# motherboard_v1.net
KiCad netlist of a schematic drawn in EAGLE
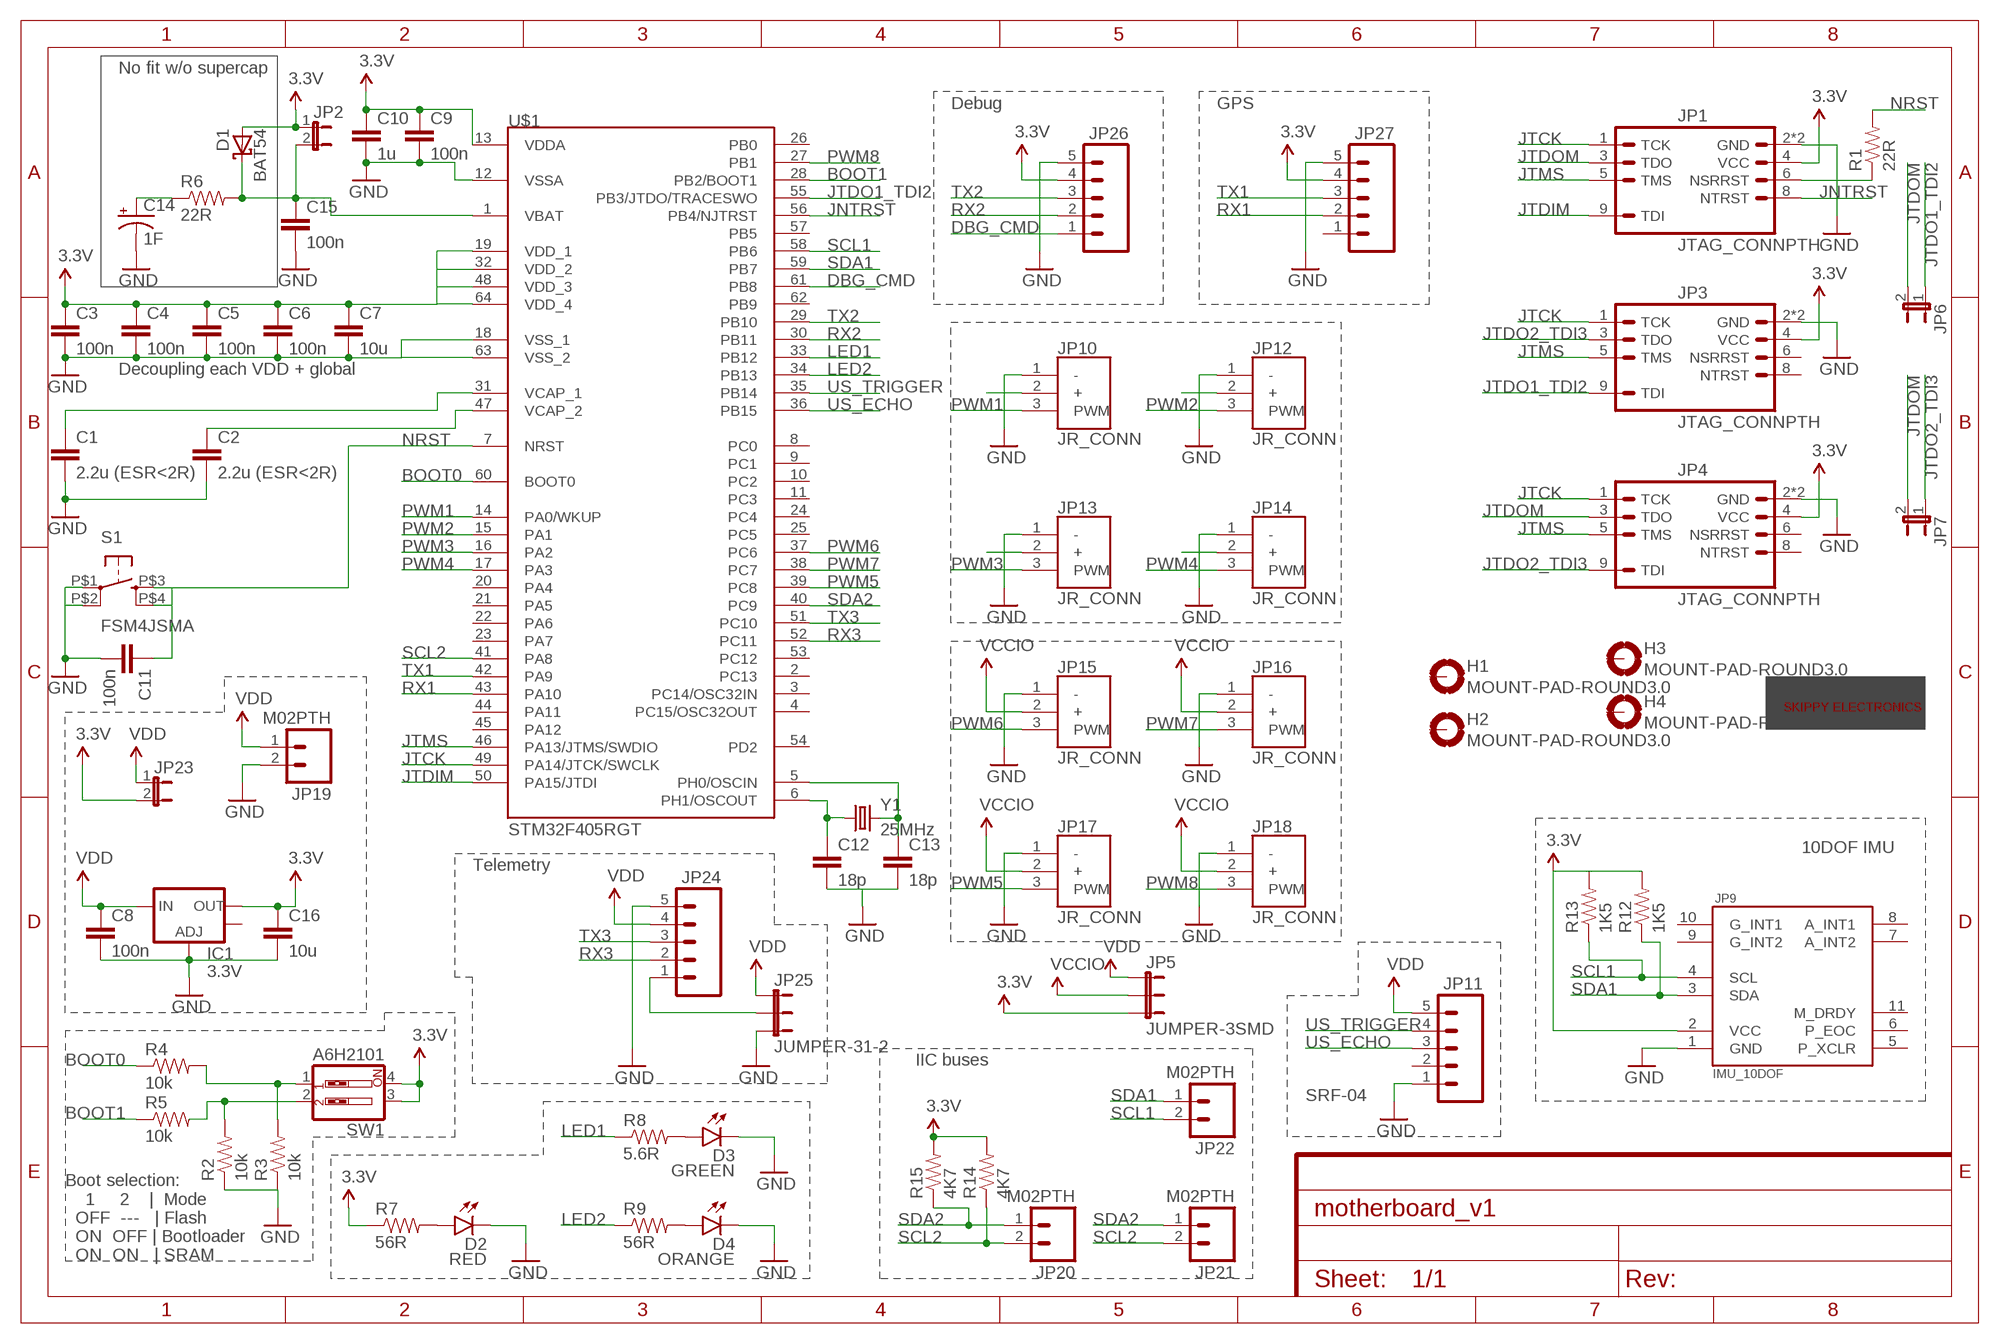
[diagram p0: schematic, sheet 1]

(export (version "E")
  (design (tool "Eeschema 10.0.6"))
  (components
    (comp (ref "C1")
      (value "2.2u (ESR<2R)")
      (footprint "eagle-import:1206")
      (libsource (lib "eagle-import") (part "CAP1206"))
    )
    (comp (ref "C2")
      (value "2.2u (ESR<2R)")
      (footprint "eagle-import:1206")
      (libsource (lib "eagle-import") (part "CAP1206"))
    )
    (comp (ref "C3")
      (value "100n")
      (footprint "eagle-import:0805")
      (libsource (lib "eagle-import") (part "CAP0805"))
    )
    (comp (ref "C4")
      (value "100n")
      (footprint "eagle-import:0805")
      (libsource (lib "eagle-import") (part "CAP0805"))
    )
    (comp (ref "C5")
      (value "100n")
      (footprint "eagle-import:0805")
      (libsource (lib "eagle-import") (part "CAP0805"))
    )
    (comp (ref "C6")
      (value "100n")
      (footprint "eagle-import:0805")
      (libsource (lib "eagle-import") (part "CAP0805"))
    )
    (comp (ref "C7")
      (value "10u")
      (footprint "eagle-import:1206")
      (libsource (lib "eagle-import") (part "CAP1206"))
    )
    (comp (ref "C8")
      (value "100n")
      (footprint "eagle-import:1206")
      (libsource (lib "eagle-import") (part "CAP1206"))
    )
    (comp (ref "C9")
      (value "100n")
      (footprint "eagle-import:0805")
      (libsource (lib "eagle-import") (part "CAP0805"))
    )
    (comp (ref "C10")
      (value "1u")
      (footprint "eagle-import:1206")
      (libsource (lib "eagle-import") (part "CAP1206"))
    )
    (comp (ref "C11")
      (value "100n")
      (footprint "eagle-import:1206")
      (libsource (lib "eagle-import") (part "CAP1206"))
    )
    (comp (ref "C12")
      (value "18p")
      (footprint "eagle-import:1206")
      (libsource (lib "eagle-import") (part "CAP1206"))
    )
    (comp (ref "C13")
      (value "18p")
      (footprint "eagle-import:1206")
      (libsource (lib "eagle-import") (part "CAP1206"))
    )
    (comp (ref "C14")
      (value "1F")
      (footprint "eagle-import:CPOL-RADIAL-D165-P508")
      (libsource (lib "eagle-import") (part "SUPERCAP"))
    )
    (comp (ref "C15")
      (value "100n")
      (footprint "eagle-import:0805")
      (libsource (lib "eagle-import") (part "CAP0805"))
    )
    (comp (ref "C16")
      (value "10u")
      (footprint "eagle-import:1206")
      (libsource (lib "eagle-import") (part "CAP1206"))
    )
    (comp (ref "D1")
      (value "BAT54")
      (footprint "eagle-import:SOT23")
      (libsource (lib "eagle-import") (part "BAT54"))
    )
    (comp (ref "D2")
      (value "RED")
      (footprint "eagle-import:LED-1206")
      (libsource (lib "eagle-import") (part "LED1206"))
    )
    (comp (ref "D3")
      (value "GREEN")
      (footprint "eagle-import:LED-1206")
      (libsource (lib "eagle-import") (part "LED1206"))
    )
    (comp (ref "D4")
      (value "ORANGE")
      (footprint "eagle-import:LED-1206")
      (libsource (lib "eagle-import") (part "LED1206"))
    )
    (comp (ref "H1")
      (value "MOUNT-PAD-ROUND3.0")
      (footprint "eagle-import:3,0-PAD")
      (libsource (lib "eagle-import") (part "MOUNT-PAD-ROUND3.0"))
    )
    (comp (ref "H2")
      (value "MOUNT-PAD-ROUND3.0")
      (footprint "eagle-import:3,0-PAD")
      (libsource (lib "eagle-import") (part "MOUNT-PAD-ROUND3.0"))
    )
    (comp (ref "H3")
      (value "MOUNT-PAD-ROUND3.0")
      (footprint "eagle-import:3,0-PAD")
      (libsource (lib "eagle-import") (part "MOUNT-PAD-ROUND3.0"))
    )
    (comp (ref "H4")
      (value "MOUNT-PAD-ROUND3.0")
      (footprint "eagle-import:3,0-PAD")
      (libsource (lib "eagle-import") (part "MOUNT-PAD-ROUND3.0"))
    )
    (comp (ref "IC1")
      (value "3.3V")
      (footprint "eagle-import:SOT223")
      (libsource (lib "eagle-import") (part "V_REG_LM1117SOT223"))
    )
    (comp (ref "JP1")
      (value "JTAG_CONNPTH")
      (footprint "eagle-import:AVR_ICSP")
      (libsource (lib "eagle-import") (part "JTAG_CONNPTH"))
    )
    (comp (ref "JP2")
      (value "JUMPER-2SMD-NO")
      (footprint "eagle-import:SJ_2S-NO")
      (libsource (lib "eagle-import") (part "JUMPER-2SMD-NO"))
    )
    (comp (ref "JP3")
      (value "JTAG_CONNPTH")
      (footprint "eagle-import:AVR_ICSP")
      (libsource (lib "eagle-import") (part "JTAG_CONNPTH"))
    )
    (comp (ref "JP4")
      (value "JTAG_CONNPTH")
      (footprint "eagle-import:AVR_ICSP")
      (libsource (lib "eagle-import") (part "JTAG_CONNPTH"))
    )
    (comp (ref "JP5")
      (value "JUMPER-3SMD")
      (footprint "eagle-import:SJ_3")
      (libsource (lib "eagle-import") (part "JUMPER-3SMD"))
    )
    (comp (ref "JP6")
      (value "JUMPER-2SMD-NO")
      (footprint "eagle-import:SJ_2S-NO")
      (libsource (lib "eagle-import") (part "JUMPER-2SMD-NO"))
    )
    (comp (ref "JP7")
      (value "JUMPER-2SMD-NO")
      (footprint "eagle-import:SJ_2S-NO")
      (libsource (lib "eagle-import") (part "JUMPER-2SMD-NO"))
    )
    (comp (ref "JP9")
      (value "IMU_10DOF")
      (footprint "eagle-import:IMU_10DOF")
      (libsource (lib "eagle-import") (part "IMU_10DOF"))
    )
    (comp (ref "JP10")
      (value "JR_CONN")
      (footprint "eagle-import:1X03")
      (libsource (lib "eagle-import") (part "JR_CONN"))
    )
    (comp (ref "JP11")
      (value "M05PTH")
      (footprint "eagle-import:1X05")
      (libsource (lib "eagle-import") (part "M05PTH"))
    )
    (comp (ref "JP12")
      (value "JR_CONN")
      (footprint "eagle-import:1X03")
      (libsource (lib "eagle-import") (part "JR_CONN"))
    )
    (comp (ref "JP13")
      (value "JR_CONN")
      (footprint "eagle-import:1X03")
      (libsource (lib "eagle-import") (part "JR_CONN"))
    )
    (comp (ref "JP14")
      (value "JR_CONN")
      (footprint "eagle-import:1X03")
      (libsource (lib "eagle-import") (part "JR_CONN"))
    )
    (comp (ref "JP15")
      (value "JR_CONN")
      (footprint "eagle-import:1X03")
      (libsource (lib "eagle-import") (part "JR_CONN"))
    )
    (comp (ref "JP16")
      (value "JR_CONN")
      (footprint "eagle-import:1X03")
      (libsource (lib "eagle-import") (part "JR_CONN"))
    )
    (comp (ref "JP17")
      (value "JR_CONN")
      (footprint "eagle-import:1X03")
      (libsource (lib "eagle-import") (part "JR_CONN"))
    )
    (comp (ref "JP18")
      (value "JR_CONN")
      (footprint "eagle-import:1X03")
      (libsource (lib "eagle-import") (part "JR_CONN"))
    )
    (comp (ref "JP19")
      (value "M02PTH")
      (footprint "eagle-import:1X02")
      (libsource (lib "eagle-import") (part "M02PTH"))
    )
    (comp (ref "JP20")
      (value "M02PTH")
      (footprint "eagle-import:1X02")
      (libsource (lib "eagle-import") (part "M02PTH"))
    )
    (comp (ref "JP21")
      (value "M02PTH")
      (footprint "eagle-import:1X02")
      (libsource (lib "eagle-import") (part "M02PTH"))
    )
    (comp (ref "JP22")
      (value "M02PTH")
      (footprint "eagle-import:1X02")
      (libsource (lib "eagle-import") (part "M02PTH"))
    )
    (comp (ref "JP23")
      (value "JUMPER-2SMD-NO")
      (footprint "eagle-import:SJ_2S-NO")
      (libsource (lib "eagle-import") (part "JUMPER-2SMD-NO"))
    )
    (comp (ref "JP24")
      (value "M05PTH")
      (footprint "eagle-import:1X05")
      (libsource (lib "eagle-import") (part "M05PTH"))
    )
    (comp (ref "JP25")
      (value "JUMPER-31-2")
      (footprint "eagle-import:SJ_3_PASTE1&2")
      (libsource (lib "eagle-import") (part "JUMPER-31-2"))
    )
    (comp (ref "JP26")
      (value "M05PTH")
      (footprint "eagle-import:1X05")
      (libsource (lib "eagle-import") (part "M05PTH"))
    )
    (comp (ref "JP27")
      (value "M05PTH")
      (footprint "eagle-import:1X05")
      (libsource (lib "eagle-import") (part "M05PTH"))
    )
    (comp (ref "R1")
      (value "22R")
      (footprint "eagle-import:1206")
      (libsource (lib "eagle-import") (part "RESISTOR1206"))
    )
    (comp (ref "R2")
      (value "10k")
      (footprint "eagle-import:1206")
      (libsource (lib "eagle-import") (part "RESISTOR1206"))
    )
    (comp (ref "R3")
      (value "10k")
      (footprint "eagle-import:1206")
      (libsource (lib "eagle-import") (part "RESISTOR1206"))
    )
    (comp (ref "R4")
      (value "10k")
      (footprint "eagle-import:1206")
      (libsource (lib "eagle-import") (part "RESISTOR1206"))
    )
    (comp (ref "R5")
      (value "10k")
      (footprint "eagle-import:1206")
      (libsource (lib "eagle-import") (part "RESISTOR1206"))
    )
    (comp (ref "R6")
      (value "22R")
      (footprint "eagle-import:1206")
      (libsource (lib "eagle-import") (part "RESISTOR1206"))
    )
    (comp (ref "R7")
      (value "56R")
      (footprint "eagle-import:1206")
      (libsource (lib "eagle-import") (part "RESISTOR1206"))
    )
    (comp (ref "R8")
      (value "5.6R")
      (footprint "eagle-import:1206")
      (libsource (lib "eagle-import") (part "RESISTOR1206"))
    )
    (comp (ref "R9")
      (value "56R")
      (footprint "eagle-import:1206")
      (libsource (lib "eagle-import") (part "RESISTOR1206"))
    )
    (comp (ref "R12")
      (value "1K5")
      (footprint "eagle-import:1206")
      (libsource (lib "eagle-import") (part "RESISTOR1206"))
    )
    (comp (ref "R13")
      (value "1K5")
      (footprint "eagle-import:1206")
      (libsource (lib "eagle-import") (part "RESISTOR1206"))
    )
    (comp (ref "R14")
      (value "4K7")
      (footprint "eagle-import:1206")
      (libsource (lib "eagle-import") (part "RESISTOR1206"))
    )
    (comp (ref "R15")
      (value "4K7")
      (footprint "eagle-import:1206")
      (libsource (lib "eagle-import") (part "RESISTOR1206"))
    )
    (comp (ref "S1")
      (value "FSM4JSMA")
      (footprint "eagle-import:TYCO-FSM4JSMA")
      (libsource (lib "eagle-import") (part "TAC_SWITCH"))
    )
    (comp (ref "SW1")
      (value "A6H2101")
      (footprint "eagle-import:DIPSWITCH-02-50MIL")
      (libsource (lib "eagle-import") (part "SW_DIP-2-SMT-HALFSIZE"))
    )
    (comp (ref "U$1")
      (value "STM32F405RGT")
      (footprint "eagle-import:LQFP-ST-64-2")
      (libsource (lib "eagle-import") (part "STM32F405RGT"))
    )
    (comp (ref "U$2")
      (value "SKIPPYTXT-PLC-10MM")
      (footprint "eagle-import:SKIPPYTXT-PLC-10MM")
      (libsource (lib "eagle-import") (part "SKIPPYTXT-PLC-10MM"))
    )
    (comp (ref "Y1")
      (value "25MHz")
      (footprint "eagle-import:HC49UP")
      (libsource (lib "eagle-import") (part "CRYSTALSMD"))
    )
  )
  (nets
    (net (code "1") (name "/BOOT0") (class "Default")
      (node (ref "R4") (pin "1") (pinfunction "1_1") (pintype "passive"))
      (node (ref "U$1") (pin "60") (pinfunction "BOOT0_60") (pintype "bidirectional"))
    )
    (net (code "2") (name "/BOOT1") (class "Default")
      (node (ref "R5") (pin "1") (pinfunction "1_1") (pintype "passive"))
      (node (ref "U$1") (pin "28") (pinfunction "PB2/BOOT1_28") (pintype "bidirectional"))
    )
    (net (code "3") (name "/DBG_CMD") (class "Default")
      (node (ref "JP26") (pin "1") (pinfunction "1_1") (pintype "passive"))
      (node (ref "U$1") (pin "61") (pinfunction "PB8_61") (pintype "bidirectional"))
    )
    (net (code "4") (name "/JNTRST") (class "Default")
      (node (ref "JP1") (pin "8") (pinfunction "NTRST_8") (pintype "passive"))
      (node (ref "U$1") (pin "56") (pinfunction "PB4/NJTRST_56") (pintype "bidirectional"))
    )
    (net (code "5") (name "/JTCK") (class "Default")
      (node (ref "JP1") (pin "1") (pinfunction "TCK_1") (pintype "passive"))
      (node (ref "JP3") (pin "1") (pinfunction "TCK_1") (pintype "passive"))
      (node (ref "JP4") (pin "1") (pinfunction "TCK_1") (pintype "passive"))
      (node (ref "U$1") (pin "49") (pinfunction "PA14/JTCK/SWCLK_49") (pintype "bidirectional"))
    )
    (net (code "6") (name "/JTDIM") (class "Default")
      (node (ref "JP1") (pin "9") (pinfunction "TDI_9") (pintype "passive"))
      (node (ref "U$1") (pin "50") (pinfunction "PA15/JTDI_50") (pintype "bidirectional"))
    )
    (net (code "7") (name "/JTDO1_TDI2") (class "Default")
      (node (ref "JP3") (pin "9") (pinfunction "TDI_9") (pintype "passive"))
      (node (ref "JP6") (pin "1") (pinfunction "1_1") (pintype "passive"))
      (node (ref "U$1") (pin "55") (pinfunction "PB3/JTDO/TRACESWO_55") (pintype "bidirectional"))
    )
    (net (code "8") (name "/JTDO2_TDI3") (class "Default")
      (node (ref "JP3") (pin "3") (pinfunction "TDO_3") (pintype "passive"))
      (node (ref "JP4") (pin "9") (pinfunction "TDI_9") (pintype "passive"))
      (node (ref "JP7") (pin "1") (pinfunction "1_1") (pintype "passive"))
    )
    (net (code "9") (name "/JTDOM") (class "Default")
      (node (ref "JP1") (pin "3") (pinfunction "TDO_3") (pintype "passive"))
      (node (ref "JP4") (pin "3") (pinfunction "TDO_3") (pintype "passive"))
      (node (ref "JP6") (pin "2") (pinfunction "2_2") (pintype "passive"))
      (node (ref "JP7") (pin "2") (pinfunction "2_2") (pintype "passive"))
    )
    (net (code "10") (name "/JTMS") (class "Default")
      (node (ref "JP1") (pin "5") (pinfunction "TMS_5") (pintype "passive"))
      (node (ref "JP3") (pin "5") (pinfunction "TMS_5") (pintype "passive"))
      (node (ref "JP4") (pin "5") (pinfunction "TMS_5") (pintype "passive"))
      (node (ref "U$1") (pin "46") (pinfunction "PA13/JTMS/SWDIO_46") (pintype "bidirectional"))
    )
    (net (code "11") (name "/LED1") (class "Default")
      (node (ref "R8") (pin "1") (pinfunction "1_1") (pintype "passive"))
      (node (ref "U$1") (pin "33") (pinfunction "PB12_33") (pintype "bidirectional"))
    )
    (net (code "12") (name "/LED2") (class "Default")
      (node (ref "R9") (pin "1") (pinfunction "1_1") (pintype "passive"))
      (node (ref "U$1") (pin "34") (pinfunction "PB13_34") (pintype "bidirectional"))
    )
    (net (code "13") (name "/NRST") (class "Default")
      (node (ref "C11") (pin "1") (pinfunction "1_1") (pintype "passive"))
      (node (ref "R1") (pin "2") (pinfunction "2_2") (pintype "passive"))
      (node (ref "S1") (pin "P$3") (pinfunction "3_P$3") (pintype "passive"))
      (node (ref "S1") (pin "P$4") (pinfunction "4_P$4") (pintype "passive"))
      (node (ref "U$1") (pin "7") (pinfunction "NRST_7") (pintype "bidirectional"))
    )
    (net (code "14") (name "/PWM1") (class "Default")
      (node (ref "JP10") (pin "3") (pinfunction "PWM_3") (pintype "bidirectional"))
      (node (ref "U$1") (pin "14") (pinfunction "PA0/WKUP_14") (pintype "bidirectional"))
    )
    (net (code "15") (name "/PWM2") (class "Default")
      (node (ref "JP12") (pin "3") (pinfunction "PWM_3") (pintype "bidirectional"))
      (node (ref "U$1") (pin "15") (pinfunction "PA1_15") (pintype "bidirectional"))
    )
    (net (code "16") (name "/PWM3") (class "Default")
      (node (ref "JP13") (pin "3") (pinfunction "PWM_3") (pintype "bidirectional"))
      (node (ref "U$1") (pin "16") (pinfunction "PA2_16") (pintype "bidirectional"))
    )
    (net (code "17") (name "/PWM4") (class "Default")
      (node (ref "JP14") (pin "3") (pinfunction "PWM_3") (pintype "bidirectional"))
      (node (ref "U$1") (pin "17") (pinfunction "PA3_17") (pintype "bidirectional"))
    )
    (net (code "18") (name "/PWM5") (class "Default")
      (node (ref "JP17") (pin "3") (pinfunction "PWM_3") (pintype "bidirectional"))
      (node (ref "U$1") (pin "39") (pinfunction "PC8_39") (pintype "bidirectional"))
    )
    (net (code "19") (name "/PWM6") (class "Default")
      (node (ref "JP15") (pin "3") (pinfunction "PWM_3") (pintype "bidirectional"))
      (node (ref "U$1") (pin "37") (pinfunction "PC6_37") (pintype "bidirectional"))
    )
    (net (code "20") (name "/PWM7") (class "Default")
      (node (ref "JP16") (pin "3") (pinfunction "PWM_3") (pintype "bidirectional"))
      (node (ref "U$1") (pin "38") (pinfunction "PC7_38") (pintype "bidirectional"))
    )
    (net (code "21") (name "/PWM8") (class "Default")
      (node (ref "JP18") (pin "3") (pinfunction "PWM_3") (pintype "bidirectional"))
      (node (ref "U$1") (pin "27") (pinfunction "PB1_27") (pintype "bidirectional"))
    )
    (net (code "22") (name "/RX1") (class "Default")
      (node (ref "JP27") (pin "2") (pinfunction "2_2") (pintype "passive"))
      (node (ref "U$1") (pin "43") (pinfunction "PA10_43") (pintype "bidirectional"))
    )
    (net (code "23") (name "/RX2") (class "Default")
      (node (ref "JP26") (pin "2") (pinfunction "2_2") (pintype "passive"))
      (node (ref "U$1") (pin "30") (pinfunction "PB11_30") (pintype "bidirectional"))
    )
    (net (code "24") (name "/RX3") (class "Default")
      (node (ref "JP24") (pin "2") (pinfunction "2_2") (pintype "passive"))
      (node (ref "U$1") (pin "52") (pinfunction "PC11_52") (pintype "bidirectional"))
    )
    (net (code "25") (name "/SCL1") (class "Default")
      (node (ref "JP22") (pin "2") (pinfunction "2_2") (pintype "passive"))
      (node (ref "JP9") (pin "4") (pinfunction "SCL_4") (pintype "input"))
      (node (ref "R13") (pin "1") (pinfunction "1_1") (pintype "passive"))
      (node (ref "U$1") (pin "58") (pinfunction "PB6_58") (pintype "bidirectional"))
    )
    (net (code "26") (name "/SCL2") (class "Default")
      (node (ref "JP20") (pin "2") (pinfunction "2_2") (pintype "passive"))
      (node (ref "JP21") (pin "2") (pinfunction "2_2") (pintype "passive"))
      (node (ref "R14") (pin "1") (pinfunction "1_1") (pintype "passive"))
      (node (ref "U$1") (pin "41") (pinfunction "PA8_41") (pintype "bidirectional"))
    )
    (net (code "27") (name "/SDA1") (class "Default")
      (node (ref "JP22") (pin "1") (pinfunction "1_1") (pintype "passive"))
      (node (ref "JP9") (pin "3") (pinfunction "SDA_3") (pintype "bidirectional"))
      (node (ref "R12") (pin "1") (pinfunction "1_1") (pintype "passive"))
      (node (ref "U$1") (pin "59") (pinfunction "PB7_59") (pintype "bidirectional"))
    )
    (net (code "28") (name "/SDA2") (class "Default")
      (node (ref "JP20") (pin "1") (pinfunction "1_1") (pintype "passive"))
      (node (ref "JP21") (pin "1") (pinfunction "1_1") (pintype "passive"))
      (node (ref "R15") (pin "1") (pinfunction "1_1") (pintype "passive"))
      (node (ref "U$1") (pin "40") (pinfunction "PC9_40") (pintype "bidirectional"))
    )
    (net (code "29") (name "/TX1") (class "Default")
      (node (ref "JP27") (pin "3") (pinfunction "3_3") (pintype "passive"))
      (node (ref "U$1") (pin "42") (pinfunction "PA9_42") (pintype "bidirectional"))
    )
    (net (code "30") (name "/TX2") (class "Default")
      (node (ref "JP26") (pin "3") (pinfunction "3_3") (pintype "passive"))
      (node (ref "U$1") (pin "29") (pinfunction "PB10_29") (pintype "bidirectional"))
    )
    (net (code "31") (name "/TX3") (class "Default")
      (node (ref "JP24") (pin "3") (pinfunction "3_3") (pintype "passive"))
      (node (ref "U$1") (pin "51") (pinfunction "PC10_51") (pintype "bidirectional"))
    )
    (net (code "32") (name "/US_ECHO") (class "Default")
      (node (ref "JP11") (pin "3") (pinfunction "3_3") (pintype "passive"))
      (node (ref "U$1") (pin "36") (pinfunction "PB15_36") (pintype "bidirectional"))
    )
    (net (code "33") (name "/US_TRIGGER") (class "Default")
      (node (ref "JP11") (pin "4") (pinfunction "4_4") (pintype "passive"))
      (node (ref "U$1") (pin "35") (pinfunction "PB14_35") (pintype "bidirectional"))
    )
    (net (code "34") (name "3.3V") (class "Default")
      (node (ref "C10") (pin "1") (pinfunction "1_1") (pintype "passive"))
      (node (ref "C16") (pin "1") (pinfunction "1_1") (pintype "passive"))
      (node (ref "C3") (pin "1") (pinfunction "1_1") (pintype "passive"))
      (node (ref "C4") (pin "1") (pinfunction "1_1") (pintype "passive"))
      (node (ref "C5") (pin "1") (pinfunction "1_1") (pintype "passive"))
      (node (ref "C6") (pin "1") (pinfunction "1_1") (pintype "passive"))
      (node (ref "C7") (pin "1") (pinfunction "1_1") (pintype "passive"))
      (node (ref "C9") (pin "1") (pinfunction "1_1") (pintype "passive"))
      (node (ref "D1") (pin "1") (pinfunction "A_1") (pintype "passive"))
      (node (ref "IC1") (pin "2") (pinfunction "OUT_2") (pintype "output"))
      (node (ref "JP1") (pin "4") (pinfunction "VCC_4") (pintype "passive"))
      (node (ref "JP2") (pin "1") (pinfunction "1_1") (pintype "passive"))
      (node (ref "JP23") (pin "2") (pinfunction "2_2") (pintype "passive"))
      (node (ref "JP26") (pin "4") (pinfunction "4_4") (pintype "passive"))
      (node (ref "JP27") (pin "4") (pinfunction "4_4") (pintype "passive"))
      (node (ref "JP3") (pin "4") (pinfunction "VCC_4") (pintype "passive"))
      (node (ref "JP4") (pin "4") (pinfunction "VCC_4") (pintype "passive"))
      (node (ref "JP5") (pin "3") (pinfunction "3_3") (pintype "passive"))
      (node (ref "JP9") (pin "2") (pinfunction "VCC_2") (pintype "power_in"))
      (node (ref "R12") (pin "2") (pinfunction "2_2") (pintype "passive"))
      (node (ref "R13") (pin "2") (pinfunction "2_2") (pintype "passive"))
      (node (ref "R14") (pin "2") (pinfunction "2_2") (pintype "passive"))
      (node (ref "R15") (pin "2") (pinfunction "2_2") (pintype "passive"))
      (node (ref "R7") (pin "1") (pinfunction "1_1") (pintype "passive"))
      (node (ref "SW1") (pin "3") (pinfunction "3_3") (pintype "passive"))
      (node (ref "SW1") (pin "4") (pinfunction "4_4") (pintype "passive"))
      (node (ref "U$1") (pin "13") (pinfunction "VDDA_13") (pintype "power_in"))
      (node (ref "U$1") (pin "19") (pinfunction "VDD_1_19") (pintype "power_in"))
      (node (ref "U$1") (pin "32") (pinfunction "VDD_2_32") (pintype "power_in"))
      (node (ref "U$1") (pin "48") (pinfunction "VDD_3_48") (pintype "power_in"))
      (node (ref "U$1") (pin "64") (pinfunction "VDD_4_64") (pintype "power_in"))
    )
    (net (code "35") (name "GND") (class "Default")
      (node (ref "C1") (pin "2") (pinfunction "2_2") (pintype "passive"))
      (node (ref "C10") (pin "2") (pinfunction "2_2") (pintype "passive"))
      (node (ref "C11") (pin "2") (pinfunction "2_2") (pintype "passive"))
      (node (ref "C12") (pin "2") (pinfunction "2_2") (pintype "passive"))
      (node (ref "C13") (pin "2") (pinfunction "2_2") (pintype "passive"))
      (node (ref "C14") (pin "2") (pinfunction "-_2") (pintype "passive"))
      (node (ref "C15") (pin "2") (pinfunction "2_2") (pintype "passive"))
      (node (ref "C16") (pin "2") (pinfunction "2_2") (pintype "passive"))
      (node (ref "C2") (pin "2") (pinfunction "2_2") (pintype "passive"))
      (node (ref "C3") (pin "2") (pinfunction "2_2") (pintype "passive"))
      (node (ref "C4") (pin "2") (pinfunction "2_2") (pintype "passive"))
      (node (ref "C5") (pin "2") (pinfunction "2_2") (pintype "passive"))
      (node (ref "C6") (pin "2") (pinfunction "2_2") (pintype "passive"))
      (node (ref "C7") (pin "2") (pinfunction "2_2") (pintype "passive"))
      (node (ref "C8") (pin "2") (pinfunction "2_2") (pintype "passive"))
      (node (ref "C9") (pin "2") (pinfunction "2_2") (pintype "passive"))
      (node (ref "D2") (pin "C") (pinfunction "C_C") (pintype "passive"))
      (node (ref "D3") (pin "C") (pinfunction "C_C") (pintype "passive"))
      (node (ref "D4") (pin "C") (pinfunction "C_C") (pintype "passive"))
      (node (ref "IC1") (pin "1") (pinfunction "ADJ_1") (pintype "input"))
      (node (ref "JP1") (pin "10") (pinfunction "GND_10") (pintype "power_in"))
      (node (ref "JP1") (pin "2") (pinfunction "GND_2") (pintype "power_in"))
      (node (ref "JP10") (pin "1") (pinfunction "-_1") (pintype "power_in"))
      (node (ref "JP11") (pin "1") (pinfunction "1_1") (pintype "passive"))
      (node (ref "JP12") (pin "1") (pinfunction "-_1") (pintype "power_in"))
      (node (ref "JP13") (pin "1") (pinfunction "-_1") (pintype "power_in"))
      (node (ref "JP14") (pin "1") (pinfunction "-_1") (pintype "power_in"))
      (node (ref "JP15") (pin "1") (pinfunction "-_1") (pintype "power_in"))
      (node (ref "JP16") (pin "1") (pinfunction "-_1") (pintype "power_in"))
      (node (ref "JP17") (pin "1") (pinfunction "-_1") (pintype "power_in"))
      (node (ref "JP18") (pin "1") (pinfunction "-_1") (pintype "power_in"))
      (node (ref "JP19") (pin "2") (pinfunction "2_2") (pintype "passive"))
      (node (ref "JP24") (pin "5") (pinfunction "5_5") (pintype "passive"))
      (node (ref "JP25") (pin "3") (pinfunction "3_3") (pintype "passive"))
      (node (ref "JP26") (pin "5") (pinfunction "5_5") (pintype "passive"))
      (node (ref "JP27") (pin "5") (pinfunction "5_5") (pintype "passive"))
      (node (ref "JP3") (pin "10") (pinfunction "GND_10") (pintype "power_in"))
      (node (ref "JP3") (pin "2") (pinfunction "GND_2") (pintype "power_in"))
      (node (ref "JP4") (pin "10") (pinfunction "GND_10") (pintype "power_in"))
      (node (ref "JP4") (pin "2") (pinfunction "GND_2") (pintype "power_in"))
      (node (ref "JP9") (pin "1") (pinfunction "GND_1") (pintype "power_in"))
      (node (ref "R2") (pin "1") (pinfunction "1_1") (pintype "passive"))
      (node (ref "R3") (pin "1") (pinfunction "1_1") (pintype "passive"))
      (node (ref "S1") (pin "P$1") (pinfunction "1_P$1") (pintype "passive"))
      (node (ref "S1") (pin "P$2") (pinfunction "2_P$2") (pintype "passive"))
      (node (ref "U$1") (pin "12") (pinfunction "VSSA_12") (pintype "power_in"))
      (node (ref "U$1") (pin "18") (pinfunction "VSS_1_18") (pintype "power_in"))
      (node (ref "U$1") (pin "63") (pinfunction "VSS_2_63") (pintype "power_in"))
    )
    (net (code "36") (name "Net-(C14-+)") (class "Default")
      (node (ref "C14") (pin "1") (pinfunction "+_1") (pintype "passive"))
      (node (ref "R6") (pin "1") (pinfunction "1_1") (pintype "passive"))
    )
    (net (code "37") (name "Net-(D1-C)") (class "Default")
      (node (ref "C15") (pin "1") (pinfunction "1_1") (pintype "passive"))
      (node (ref "D1") (pin "3") (pinfunction "C_3") (pintype "passive"))
      (node (ref "JP2") (pin "2") (pinfunction "2_2") (pintype "passive"))
      (node (ref "R6") (pin "2") (pinfunction "2_2") (pintype "passive"))
      (node (ref "U$1") (pin "1") (pinfunction "VBAT_1") (pintype "power_in"))
    )
    (net (code "38") (name "Net-(D2-PadA)") (class "Default")
      (node (ref "D2") (pin "A") (pinfunction "A_A") (pintype "passive"))
      (node (ref "R7") (pin "2") (pinfunction "2_2") (pintype "passive"))
    )
    (net (code "39") (name "Net-(D3-PadA)") (class "Default")
      (node (ref "D3") (pin "A") (pinfunction "A_A") (pintype "passive"))
      (node (ref "R8") (pin "2") (pinfunction "2_2") (pintype "passive"))
    )
    (net (code "40") (name "Net-(D4-PadA)") (class "Default")
      (node (ref "D4") (pin "A") (pinfunction "A_A") (pintype "passive"))
      (node (ref "R9") (pin "2") (pinfunction "2_2") (pintype "passive"))
    )
    (net (code "41") (name "Net-(JP1-NSRRST)") (class "Default")
      (node (ref "JP1") (pin "6") (pinfunction "NSRRST_6") (pintype "passive"))
      (node (ref "R1") (pin "1") (pinfunction "1_1") (pintype "passive"))
    )
    (net (code "42") (name "Net-(JP24-Pad1)") (class "Default")
      (node (ref "JP24") (pin "1") (pinfunction "1_1") (pintype "passive"))
      (node (ref "JP25") (pin "2") (pinfunction "2_2") (pintype "passive"))
    )
    (net (code "43") (name "Net-(R2-Pad2)") (class "Default")
      (node (ref "R2") (pin "2") (pinfunction "2_2") (pintype "passive"))
      (node (ref "R5") (pin "2") (pinfunction "2_2") (pintype "passive"))
      (node (ref "SW1") (pin "2") (pinfunction "2_2") (pintype "passive"))
    )
    (net (code "44") (name "Net-(R3-Pad2)") (class "Default")
      (node (ref "R3") (pin "2") (pinfunction "2_2") (pintype "passive"))
      (node (ref "R4") (pin "2") (pinfunction "2_2") (pintype "passive"))
      (node (ref "SW1") (pin "1") (pinfunction "1_1") (pintype "passive"))
    )
    (net (code "45") (name "Net-(U$1-PH0{slash}OSCIN)") (class "Default")
      (node (ref "C13") (pin "1") (pinfunction "1_1") (pintype "passive"))
      (node (ref "U$1") (pin "5") (pinfunction "PH0/OSCIN_5") (pintype "bidirectional"))
      (node (ref "Y1") (pin "2") (pinfunction "2_2") (pintype "passive"))
    )
    (net (code "46") (name "Net-(U$1-PH1{slash}OSCOUT)") (class "Default")
      (node (ref "C12") (pin "1") (pinfunction "1_1") (pintype "passive"))
      (node (ref "U$1") (pin "6") (pinfunction "PH1/OSCOUT_6") (pintype "bidirectional"))
      (node (ref "Y1") (pin "1") (pinfunction "1_1") (pintype "passive"))
    )
    (net (code "47") (name "Net-(U$1-VCAP_1)") (class "Default")
      (node (ref "C1") (pin "1") (pinfunction "1_1") (pintype "passive"))
      (node (ref "U$1") (pin "31") (pinfunction "VCAP_1_31") (pintype "power_in"))
    )
    (net (code "48") (name "Net-(U$1-VCAP_2)") (class "Default")
      (node (ref "C2") (pin "1") (pinfunction "1_1") (pintype "passive"))
      (node (ref "U$1") (pin "47") (pinfunction "VCAP_2_47") (pintype "power_in"))
    )
    (net (code "49") (name "VCCIO") (class "Default")
      (node (ref "JP15") (pin "2") (pinfunction "+_2") (pintype "power_in"))
      (node (ref "JP16") (pin "2") (pinfunction "+_2") (pintype "power_in"))
      (node (ref "JP17") (pin "2") (pinfunction "+_2") (pintype "power_in"))
      (node (ref "JP18") (pin "2") (pinfunction "+_2") (pintype "power_in"))
      (node (ref "JP5") (pin "2") (pinfunction "2_2") (pintype "passive"))
    )
    (net (code "50") (name "VDD") (class "Default")
      (node (ref "C8") (pin "1") (pinfunction "1_1") (pintype "passive"))
      (node (ref "IC1") (pin "3") (pinfunction "IN_3") (pintype "input"))
      (node (ref "JP11") (pin "5") (pinfunction "5_5") (pintype "passive"))
      (node (ref "JP19") (pin "1") (pinfunction "1_1") (pintype "passive"))
      (node (ref "JP23") (pin "1") (pinfunction "1_1") (pintype "passive"))
      (node (ref "JP24") (pin "4") (pinfunction "4_4") (pintype "passive"))
      (node (ref "JP25") (pin "1") (pinfunction "1_1") (pintype "passive"))
      (node (ref "JP5") (pin "1") (pinfunction "1_1") (pintype "passive"))
    )
    (net (code "51") (name "unconnected-(H1-MOUNT-PadB3,0)") (class "Default")
      (node (ref "H1") (pin "B3,0") (pinfunction "MOUNT_B3,0") (pintype "passive"))
    )
    (net (code "52") (name "unconnected-(H2-MOUNT-PadB3,0)") (class "Default")
      (node (ref "H2") (pin "B3,0") (pinfunction "MOUNT_B3,0") (pintype "passive"))
    )
    (net (code "53") (name "unconnected-(H3-MOUNT-PadB3,0)") (class "Default")
      (node (ref "H3") (pin "B3,0") (pinfunction "MOUNT_B3,0") (pintype "passive"))
    )
    (net (code "54") (name "unconnected-(H4-MOUNT-PadB3,0)") (class "Default")
      (node (ref "H4") (pin "B3,0") (pinfunction "MOUNT_B3,0") (pintype "passive"))
    )
    (net (code "55") (name "unconnected-(IC1-OUT-Pad4)") (class "Default")
      (node (ref "IC1") (pin "4") (pinfunction "OUT_4") (pintype "output"))
    )
    (net (code "56") (name "unconnected-(JP3-NSRRST-Pad6)") (class "Default")
      (node (ref "JP3") (pin "6") (pinfunction "NSRRST_6") (pintype "passive"))
    )
    (net (code "57") (name "unconnected-(JP3-NTRST-Pad8)") (class "Default")
      (node (ref "JP3") (pin "8") (pinfunction "NTRST_8") (pintype "passive"))
    )
    (net (code "58") (name "unconnected-(JP4-NSRRST-Pad6)") (class "Default")
      (node (ref "JP4") (pin "6") (pinfunction "NSRRST_6") (pintype "passive"))
    )
    (net (code "59") (name "unconnected-(JP4-NTRST-Pad8)") (class "Default")
      (node (ref "JP4") (pin "8") (pinfunction "NTRST_8") (pintype "passive"))
    )
    (net (code "60") (name "unconnected-(JP9-A_INT1-Pad8)") (class "Default")
      (node (ref "JP9") (pin "8") (pinfunction "A_INT1_8") (pintype "output"))
    )
    (net (code "61") (name "unconnected-(JP9-A_INT2-Pad7)") (class "Default")
      (node (ref "JP9") (pin "7") (pinfunction "A_INT2_7") (pintype "output"))
    )
    (net (code "62") (name "unconnected-(JP9-G_INT1-Pad10)") (class "Default")
      (node (ref "JP9") (pin "10") (pinfunction "G_INT1_10") (pintype "output"))
    )
    (net (code "63") (name "unconnected-(JP9-G_INT2-Pad9)") (class "Default")
      (node (ref "JP9") (pin "9") (pinfunction "G_INT2_9") (pintype "output"))
    )
    (net (code "64") (name "unconnected-(JP9-M_DRDY-Pad11)") (class "Default")
      (node (ref "JP9") (pin "11") (pinfunction "M_DRDY_11") (pintype "output"))
    )
    (net (code "65") (name "unconnected-(JP9-P_EOC-Pad6)") (class "Default")
      (node (ref "JP9") (pin "6") (pinfunction "P_EOC_6") (pintype "bidirectional"))
    )
    (net (code "66") (name "unconnected-(JP9-P_XCLR-Pad5)") (class "Default")
      (node (ref "JP9") (pin "5") (pinfunction "P_XCLR_5") (pintype "bidirectional"))
    )
    (net (code "67") (name "unconnected-(JP10-+-Pad2)") (class "Default")
      (node (ref "JP10") (pin "2") (pinfunction "+_2") (pintype "power_in"))
    )
    (net (code "68") (name "unconnected-(JP11-Pad2)") (class "Default")
      (node (ref "JP11") (pin "2") (pinfunction "2_2") (pintype "passive"))
    )
    (net (code "69") (name "unconnected-(JP12-+-Pad2)") (class "Default")
      (node (ref "JP12") (pin "2") (pinfunction "+_2") (pintype "power_in"))
    )
    (net (code "70") (name "unconnected-(JP13-+-Pad2)") (class "Default")
      (node (ref "JP13") (pin "2") (pinfunction "+_2") (pintype "power_in"))
    )
    (net (code "71") (name "unconnected-(JP14-+-Pad2)") (class "Default")
      (node (ref "JP14") (pin "2") (pinfunction "+_2") (pintype "power_in"))
    )
    (net (code "72") (name "unconnected-(JP27-Pad1)") (class "Default")
      (node (ref "JP27") (pin "1") (pinfunction "1_1") (pintype "passive"))
    )
    (net (code "73") (name "unconnected-(U$1-PA4-Pad20)") (class "Default")
      (node (ref "U$1") (pin "20") (pinfunction "PA4_20") (pintype "bidirectional"))
    )
    (net (code "74") (name "unconnected-(U$1-PA5-Pad21)") (class "Default")
      (node (ref "U$1") (pin "21") (pinfunction "PA5_21") (pintype "bidirectional"))
    )
    (net (code "75") (name "unconnected-(U$1-PA6-Pad22)") (class "Default")
      (node (ref "U$1") (pin "22") (pinfunction "PA6_22") (pintype "bidirectional"))
    )
    (net (code "76") (name "unconnected-(U$1-PA7-Pad23)") (class "Default")
      (node (ref "U$1") (pin "23") (pinfunction "PA7_23") (pintype "bidirectional"))
    )
    (net (code "77") (name "unconnected-(U$1-PA11-Pad44)") (class "Default")
      (node (ref "U$1") (pin "44") (pinfunction "PA11_44") (pintype "bidirectional"))
    )
    (net (code "78") (name "unconnected-(U$1-PA12-Pad45)") (class "Default")
      (node (ref "U$1") (pin "45") (pinfunction "PA12_45") (pintype "bidirectional"))
    )
    (net (code "79") (name "unconnected-(U$1-PB0-Pad26)") (class "Default")
      (node (ref "U$1") (pin "26") (pinfunction "PB0_26") (pintype "bidirectional"))
    )
    (net (code "80") (name "unconnected-(U$1-PB5-Pad57)") (class "Default")
      (node (ref "U$1") (pin "57") (pinfunction "PB5_57") (pintype "bidirectional"))
    )
    (net (code "81") (name "unconnected-(U$1-PB9-Pad62)") (class "Default")
      (node (ref "U$1") (pin "62") (pinfunction "PB9_62") (pintype "bidirectional"))
    )
    (net (code "82") (name "unconnected-(U$1-PC0-Pad8)") (class "Default")
      (node (ref "U$1") (pin "8") (pinfunction "PC0_8") (pintype "bidirectional"))
    )
    (net (code "83") (name "unconnected-(U$1-PC1-Pad9)") (class "Default")
      (node (ref "U$1") (pin "9") (pinfunction "PC1_9") (pintype "bidirectional"))
    )
    (net (code "84") (name "unconnected-(U$1-PC2-Pad10)") (class "Default")
      (node (ref "U$1") (pin "10") (pinfunction "PC2_10") (pintype "bidirectional"))
    )
    (net (code "85") (name "unconnected-(U$1-PC3-Pad11)") (class "Default")
      (node (ref "U$1") (pin "11") (pinfunction "PC3_11") (pintype "bidirectional"))
    )
    (net (code "86") (name "unconnected-(U$1-PC4-Pad24)") (class "Default")
      (node (ref "U$1") (pin "24") (pinfunction "PC4_24") (pintype "bidirectional"))
    )
    (net (code "87") (name "unconnected-(U$1-PC5-Pad25)") (class "Default")
      (node (ref "U$1") (pin "25") (pinfunction "PC5_25") (pintype "bidirectional"))
    )
    (net (code "88") (name "unconnected-(U$1-PC12-Pad53)") (class "Default")
      (node (ref "U$1") (pin "53") (pinfunction "PC12_53") (pintype "bidirectional"))
    )
    (net (code "89") (name "unconnected-(U$1-PC13-Pad2)") (class "Default")
      (node (ref "U$1") (pin "2") (pinfunction "PC13_2") (pintype "bidirectional"))
    )
    (net (code "90") (name "unconnected-(U$1-PC14{slash}OSC32IN-Pad3)") (class "Default")
      (node (ref "U$1") (pin "3") (pinfunction "PC14/OSC32IN_3") (pintype "bidirectional"))
    )
    (net (code "91") (name "unconnected-(U$1-PC15{slash}OSC32OUT-Pad4)") (class "Default")
      (node (ref "U$1") (pin "4") (pinfunction "PC15/OSC32OUT_4") (pintype "bidirectional"))
    )
    (net (code "92") (name "unconnected-(U$1-PD2-Pad54)") (class "Default")
      (node (ref "U$1") (pin "54") (pinfunction "PD2_54") (pintype "bidirectional"))
    )
  )
)
